# 388_Design_Project_Schematic.net
KiCad netlist of a schematic drawn in EAGLE
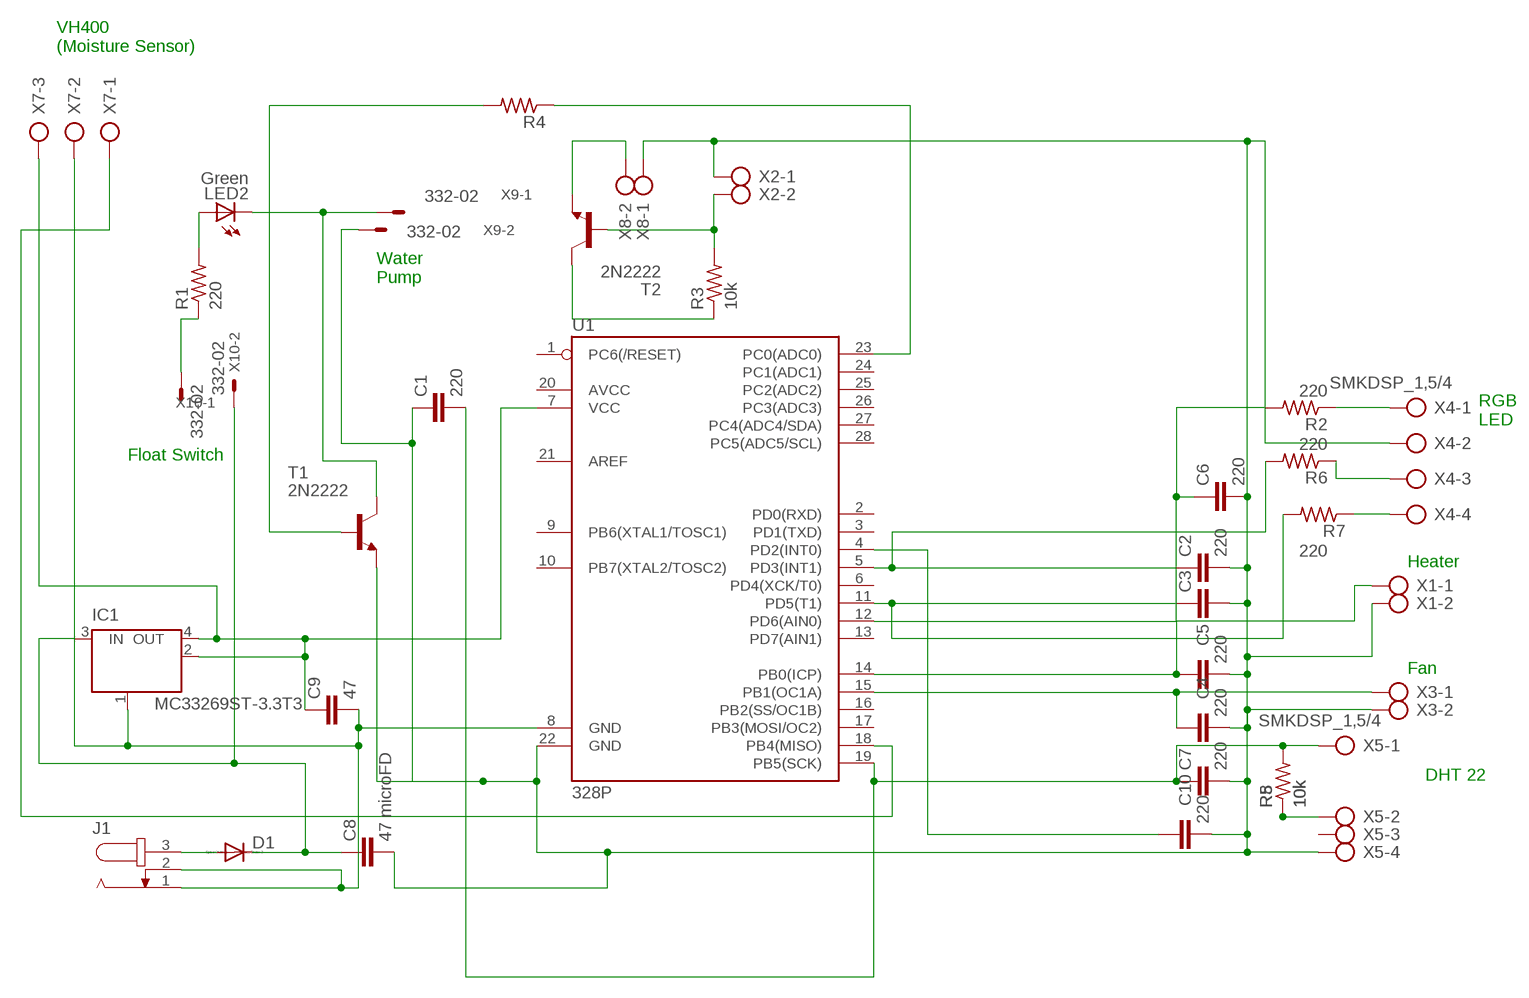
[diagram p0: schematic, sheet 1]

(export (version "E")
  (design (tool "Eeschema 10.0.6"))
  (components
    (comp (ref "C1")
      (value "220")
      (footprint "eagle-import:C025-024X044")
      (libsource (lib "eagle-import") (part "C-EU025-024X044"))
    )
    (comp (ref "C2")
      (value "220")
      (footprint "eagle-import:C025-024X044")
      (libsource (lib "eagle-import") (part "C-EU025-024X044"))
    )
    (comp (ref "C3")
      (value "C-EU025-024X044")
      (footprint "eagle-import:C025-024X044")
      (libsource (lib "eagle-import") (part "C-EU025-024X044"))
    )
    (comp (ref "C4")
      (value "220")
      (footprint "eagle-import:C025-024X044")
      (libsource (lib "eagle-import") (part "C-EU025-024X044"))
    )
    (comp (ref "C5")
      (value "220")
      (footprint "eagle-import:C025-024X044")
      (libsource (lib "eagle-import") (part "C-EU025-024X044"))
    )
    (comp (ref "C6")
      (value "220")
      (footprint "eagle-import:C025-024X044")
      (libsource (lib "eagle-import") (part "C-EU025-024X044"))
    )
    (comp (ref "C7")
      (value "220")
      (footprint "eagle-import:C025-024X044")
      (libsource (lib "eagle-import") (part "C-EU025-024X044"))
    )
    (comp (ref "C8")
      (value "47 microFD")
      (footprint "eagle-import:C025-024X044")
      (libsource (lib "eagle-import") (part "C-EU025-024X044"))
    )
    (comp (ref "C9")
      (value "47")
      (footprint "eagle-import:C025-024X044")
      (libsource (lib "eagle-import") (part "C-EU025-024X044"))
    )
    (comp (ref "C10")
      (value "220")
      (footprint "eagle-import:C025-024X044")
      (libsource (lib "eagle-import") (part "C-EU025-024X044"))
    )
    (comp (ref "D1")
      (value "DIODE-DO214BA")
      (footprint "eagle-import:DO214BA")
      (libsource (lib "eagle-import") (part "DIODE-DO214BA"))
    )
    (comp (ref "IC1")
      (value "MC33269ST-3.3T3")
      (footprint "eagle-import:SOT223")
      (libsource (lib "eagle-import") (part "MC33269ST-3.3T3"))
    )
    (comp (ref "J1")
      (value "JACK-PLUG1")
      (footprint "eagle-import:SPC4078")
      (libsource (lib "eagle-import") (part "JACK-PLUG1"))
    )
    (comp (ref "LED2")
      (value "Green")
      (footprint "eagle-import:CHIPLED_0805")
      (libsource (lib "eagle-import") (part "LEDCHIPLED_0805"))
    )
    (comp (ref "R1")
      (value "220")
      (footprint "eagle-import:R0805")
      (libsource (lib "eagle-import") (part "R-US_R0805"))
    )
    (comp (ref "R2")
      (value "220")
      (footprint "eagle-import:R0805")
      (libsource (lib "eagle-import") (part "R-US_R0805"))
    )
    (comp (ref "R3")
      (value "10k")
      (footprint "eagle-import:R0805")
      (libsource (lib "eagle-import") (part "R-US_R0805"))
    )
    (comp (ref "R4")
      (value "R-US_R0805")
      (footprint "eagle-import:R0805")
      (libsource (lib "eagle-import") (part "R-US_R0805"))
    )
    (comp (ref "R5")
      (value "10k")
      (footprint "eagle-import:R0805")
      (libsource (lib "eagle-import") (part "R-US_R0805"))
    )
    (comp (ref "R6")
      (value "220")
      (footprint "eagle-import:R0805")
      (libsource (lib "eagle-import") (part "R-US_R0805"))
    )
    (comp (ref "R7")
      (value "220")
      (footprint "eagle-import:R0805")
      (libsource (lib "eagle-import") (part "R-US_R0805"))
    )
    (comp (ref "R8")
      (value "10k")
      (footprint "eagle-import:R0805")
      (libsource (lib "eagle-import") (part "R-US_R0805"))
    )
    (comp (ref "T1")
      (value "2N2222")
      (footprint "eagle-import:TO18")
      (libsource (lib "eagle-import") (part "2N2222"))
    )
    (comp (ref "T2")
      (value "2N2222")
      (footprint "eagle-import:TO18")
      (libsource (lib "eagle-import") (part "2N2222"))
    )
    (comp (ref "U1")
      (value "328P")
      (footprint "eagle-import:DIP28")
      (libsource (lib "eagle-import") (part "ATMEGA328P_PDIP"))
    )
    (comp (ref "X1")
      (value "AK300/2")
      (footprint "eagle-import:AK300_2")
      (libsource (lib "eagle-import") (part "AK300/2"))
    )
    (comp (ref "X2")
      (value "AK300/2")
      (footprint "eagle-import:AK300_2")
      (libsource (lib "eagle-import") (part "AK300/2"))
    )
    (comp (ref "X3")
      (value "AK300/2")
      (footprint "eagle-import:AK300_2")
      (libsource (lib "eagle-import") (part "AK300/2"))
    )
    (comp (ref "X4")
      (value "SMKDSP_1,5/4")
      (footprint "eagle-import:SMKDSP_1,5_4")
      (fields (field (name "MF") "FARNELL") (field (name "MPN") "1733596"))
      (libsource (lib "eagle-import") (part "SMKDSP_1,5/4"))
    )
    (comp (ref "X5")
      (value "SMKDSP_1,5/4")
      (footprint "eagle-import:SMKDSP_1,5_4")
      (fields (field (name "MF") "FARNELL") (field (name "MPN") "1733596"))
      (libsource (lib "eagle-import") (part "SMKDSP_1,5/4"))
    )
    (comp (ref "X7")
      (value "AK300/3")
      (footprint "eagle-import:AK300_3")
      (libsource (lib "eagle-import") (part "AK300/3"))
    )
    (comp (ref "X8")
      (value "AK300/2")
      (footprint "eagle-import:AK300_2")
      (libsource (lib "eagle-import") (part "AK300/2"))
    )
    (comp (ref "X9")
      (value "332-02")
      (footprint "eagle-import:332-02")
      (libsource (lib "eagle-import") (part "332-02"))
    )
    (comp (ref "X10")
      (value "332-02")
      (footprint "eagle-import:332-02")
      (libsource (lib "eagle-import") (part "332-02"))
    )
  )
  (nets
    (net (code "1") (name "Net-(D1-PadA)") (class "Default")
      (node (ref "D1") (pin "A") (pinfunction "A_A") (pintype "passive"))
      (node (ref "J1") (pin "3") (pinfunction "3_3") (pintype "passive"))
    )
    (net (code "2") (name "Net-(IC1-GND{slash}ADJ)") (class "Default")
      (node (ref "C9") (pin "2") (pinfunction "2_2") (pintype "passive"))
      (node (ref "IC1") (pin "1") (pinfunction "GND/ADJ_1") (pintype "input"))
      (node (ref "J1") (pin "1") (pinfunction "1_1") (pintype "passive"))
      (node (ref "J1") (pin "2") (pinfunction "2_2") (pintype "passive"))
      (node (ref "U1") (pin "8") (pinfunction "GND_8") (pintype "bidirectional"))
      (node (ref "X7") (pin "2") (pinfunction "KL_2") (pintype "passive"))
    )
    (net (code "3") (name "Net-(IC1-IN)") (class "Default")
      (node (ref "C8") (pin "1") (pinfunction "1_1") (pintype "passive"))
      (node (ref "D1") (pin "C") (pinfunction "C_C") (pintype "passive"))
      (node (ref "IC1") (pin "3") (pinfunction "IN_3") (pintype "input"))
      (node (ref "X10") (pin "2") (pinfunction "S_2") (pintype "passive"))
    )
    (net (code "4") (name "Net-(LED2-PadA)") (class "Default")
      (node (ref "LED2") (pin "A") (pinfunction "A_A") (pintype "passive"))
      (node (ref "R1") (pin "2") (pinfunction "2_2") (pintype "passive"))
    )
    (net (code "5") (name "Net-(T1-B)") (class "Default")
      (node (ref "R4") (pin "2") (pinfunction "2_2") (pintype "passive"))
      (node (ref "T1") (pin "2") (pinfunction "B_2") (pintype "passive"))
    )
    (net (code "6") (name "Net-(T1-C)") (class "Default")
      (node (ref "LED2") (pin "C") (pinfunction "C_C") (pintype "passive"))
      (node (ref "T1") (pin "3") (pinfunction "C_3") (pintype "passive"))
      (node (ref "X9") (pin "1") (pinfunction "S_1") (pintype "passive"))
    )
    (net (code "7") (name "Net-(T1-E)") (class "Default")
      (node (ref "C1") (pin "1") (pinfunction "1_1") (pintype "passive"))
      (node (ref "C10") (pin "2") (pinfunction "2_2") (pintype "passive"))
      (node (ref "C2") (pin "2") (pinfunction "2_2") (pintype "passive"))
      (node (ref "C3") (pin "2") (pinfunction "2_2") (pintype "passive"))
      (node (ref "C4") (pin "2") (pinfunction "2_2") (pintype "passive"))
      (node (ref "C5") (pin "2") (pinfunction "2_2") (pintype "passive"))
      (node (ref "C6") (pin "2") (pinfunction "2_2") (pintype "passive"))
      (node (ref "C7") (pin "2") (pinfunction "2_2") (pintype "passive"))
      (node (ref "C8") (pin "2") (pinfunction "2_2") (pintype "passive"))
      (node (ref "T1") (pin "1") (pinfunction "E_1") (pintype "passive"))
      (node (ref "U1") (pin "22") (pinfunction "GND_22") (pintype "bidirectional"))
      (node (ref "X1") (pin "2") (pinfunction "KL_2") (pintype "passive"))
      (node (ref "X2") (pin "1") (pinfunction "KL_1") (pintype "passive"))
      (node (ref "X3") (pin "2") (pinfunction "KL_2") (pintype "passive"))
      (node (ref "X4") (pin "2") (pinfunction "KL_2") (pintype "passive"))
      (node (ref "X5") (pin "4") (pinfunction "KL_4") (pintype "passive"))
      (node (ref "X8") (pin "1") (pinfunction "KL_1") (pintype "passive"))
      (node (ref "X9") (pin "2") (pinfunction "S_2") (pintype "passive"))
    )
    (net (code "8") (name "Net-(T2-B)") (class "Default")
      (node (ref "R3") (pin "2") (pinfunction "2_2") (pintype "passive"))
      (node (ref "T2") (pin "2") (pinfunction "B_2") (pintype "passive"))
      (node (ref "X2") (pin "2") (pinfunction "KL_2") (pintype "passive"))
    )
    (net (code "9") (name "Net-(T2-C)") (class "Default")
      (node (ref "R3") (pin "1") (pinfunction "1_1") (pintype "passive"))
      (node (ref "T2") (pin "3") (pinfunction "C_3") (pintype "passive"))
    )
    (net (code "10") (name "Net-(T2-E)") (class "Default")
      (node (ref "T2") (pin "1") (pinfunction "E_1") (pintype "passive"))
      (node (ref "X8") (pin "2") (pinfunction "KL_2") (pintype "passive"))
    )
    (net (code "11") (name "Net-(U1-PB0(ICP))") (class "Default")
      (node (ref "C5") (pin "1") (pinfunction "1_1") (pintype "passive"))
      (node (ref "C6") (pin "1") (pinfunction "1_1") (pintype "passive"))
      (node (ref "R2") (pin "2") (pinfunction "2_2") (pintype "passive"))
      (node (ref "U1") (pin "12") (pinfunction "PD6(AIN0)_12") (pintype "bidirectional"))
      (node (ref "U1") (pin "14") (pinfunction "PB0(ICP)_14") (pintype "bidirectional"))
      (node (ref "X1") (pin "1") (pinfunction "KL_1") (pintype "passive"))
    )
    (net (code "12") (name "Net-(U1-PB1(OC1A))") (class "Default")
      (node (ref "C4") (pin "1") (pinfunction "1_1") (pintype "passive"))
      (node (ref "U1") (pin "15") (pinfunction "PB1(OC1A)_15") (pintype "bidirectional"))
      (node (ref "X3") (pin "1") (pinfunction "KL_1") (pintype "passive"))
    )
    (net (code "13") (name "Net-(U1-PB4(MISO))") (class "Default")
      (node (ref "U1") (pin "18") (pinfunction "PB4(MISO)_18") (pintype "bidirectional"))
      (node (ref "X7") (pin "1") (pinfunction "KL_1") (pintype "passive"))
    )
    (net (code "14") (name "Net-(U1-PB5(SCK))") (class "Default")
      (node (ref "C1") (pin "2") (pinfunction "2_2") (pintype "passive"))
      (node (ref "C7") (pin "1") (pinfunction "1_1") (pintype "passive"))
      (node (ref "R5") (pin "2") (pinfunction "2_2") (pintype "passive"))
      (node (ref "R8") (pin "2") (pinfunction "2_2") (pintype "passive"))
      (node (ref "U1") (pin "19") (pinfunction "PB5(SCK)_19") (pintype "bidirectional"))
      (node (ref "X5") (pin "1") (pinfunction "KL_1") (pintype "passive"))
    )
    (net (code "15") (name "Net-(U1-PC0(ADC0))") (class "Default")
      (node (ref "R4") (pin "1") (pinfunction "1_1") (pintype "passive"))
      (node (ref "U1") (pin "23") (pinfunction "PC0(ADC0)_23") (pintype "bidirectional"))
    )
    (net (code "16") (name "Net-(U1-PD2(INT0))") (class "Default")
      (node (ref "C10") (pin "1") (pinfunction "1_1") (pintype "passive"))
      (node (ref "U1") (pin "4") (pinfunction "PD2(INT0)_4") (pintype "bidirectional"))
    )
    (net (code "17") (name "Net-(U1-PD3(INT1))") (class "Default")
      (node (ref "C2") (pin "1") (pinfunction "1_1") (pintype "passive"))
      (node (ref "R6") (pin "2") (pinfunction "2_2") (pintype "passive"))
      (node (ref "U1") (pin "5") (pinfunction "PD3(INT1)_5") (pintype "bidirectional"))
    )
    (net (code "18") (name "Net-(U1-PD5(T1))") (class "Default")
      (node (ref "C3") (pin "1") (pinfunction "1_1") (pintype "passive"))
      (node (ref "R7") (pin "2") (pinfunction "2_2") (pintype "passive"))
      (node (ref "U1") (pin "11") (pinfunction "PD5(T1)_11") (pintype "bidirectional"))
    )
    (net (code "19") (name "Net-(U1-VCC)") (class "Default")
      (node (ref "C9") (pin "1") (pinfunction "1_1") (pintype "passive"))
      (node (ref "IC1") (pin "2") (pinfunction "OUT_2") (pintype "passive"))
      (node (ref "IC1") (pin "4") (pinfunction "OUT_4") (pintype "passive"))
      (node (ref "U1") (pin "7") (pinfunction "VCC_7") (pintype "bidirectional"))
      (node (ref "X7") (pin "3") (pinfunction "KL_3") (pintype "passive"))
    )
    (net (code "20") (name "Net-(X4A-KL)") (class "Default")
      (node (ref "R2") (pin "1") (pinfunction "1_1") (pintype "passive"))
      (node (ref "X4") (pin "1") (pinfunction "KL_1") (pintype "passive"))
    )
    (net (code "21") (name "Net-(X4C-KL)") (class "Default")
      (node (ref "R6") (pin "1") (pinfunction "1_1") (pintype "passive"))
      (node (ref "X4") (pin "3") (pinfunction "KL_3") (pintype "passive"))
    )
    (net (code "22") (name "Net-(X4D-KL)") (class "Default")
      (node (ref "R7") (pin "1") (pinfunction "1_1") (pintype "passive"))
      (node (ref "X4") (pin "4") (pinfunction "KL_4") (pintype "passive"))
    )
    (net (code "23") (name "Net-(X5B-KL)") (class "Default")
      (node (ref "R5") (pin "1") (pinfunction "1_1") (pintype "passive"))
      (node (ref "R8") (pin "1") (pinfunction "1_1") (pintype "passive"))
      (node (ref "X5") (pin "2") (pinfunction "KL_2") (pintype "passive"))
    )
    (net (code "24") (name "Net-(X10A-S)") (class "Default")
      (node (ref "R1") (pin "1") (pinfunction "1_1") (pintype "passive"))
      (node (ref "X10") (pin "1") (pinfunction "S_1") (pintype "passive"))
    )
    (net (code "25") (name "unconnected-(U1-AREF-Pad21)") (class "Default")
      (node (ref "U1") (pin "21") (pinfunction "AREF_21") (pintype "bidirectional"))
    )
    (net (code "26") (name "unconnected-(U1-AVCC-Pad20)") (class "Default")
      (node (ref "U1") (pin "20") (pinfunction "AVCC_20") (pintype "bidirectional"))
    )
    (net (code "27") (name "unconnected-(U1-PB2(SS{slash}OC1B)-Pad16)") (class "Default")
      (node (ref "U1") (pin "16") (pinfunction "PB2(SS/OC1B)_16") (pintype "bidirectional"))
    )
    (net (code "28") (name "unconnected-(U1-PB3(MOSI{slash}OC2)-Pad17)") (class "Default")
      (node (ref "U1") (pin "17") (pinfunction "PB3(MOSI/OC2)_17") (pintype "bidirectional"))
    )
    (net (code "29") (name "unconnected-(U1-PB6(XTAL1{slash}TOSC1)-Pad9)") (class "Default")
      (node (ref "U1") (pin "9") (pinfunction "PB6(XTAL1/TOSC1)_9") (pintype "bidirectional"))
    )
    (net (code "30") (name "unconnected-(U1-PB7(XTAL2{slash}TOSC2)-Pad10)") (class "Default")
      (node (ref "U1") (pin "10") (pinfunction "PB7(XTAL2/TOSC2)_10") (pintype "bidirectional"))
    )
    (net (code "31") (name "unconnected-(U1-PC1(ADC1)-Pad24)") (class "Default")
      (node (ref "U1") (pin "24") (pinfunction "PC1(ADC1)_24") (pintype "bidirectional"))
    )
    (net (code "32") (name "unconnected-(U1-PC2(ADC2)-Pad25)") (class "Default")
      (node (ref "U1") (pin "25") (pinfunction "PC2(ADC2)_25") (pintype "bidirectional"))
    )
    (net (code "33") (name "unconnected-(U1-PC3(ADC3)-Pad26)") (class "Default")
      (node (ref "U1") (pin "26") (pinfunction "PC3(ADC3)_26") (pintype "bidirectional"))
    )
    (net (code "34") (name "unconnected-(U1-PC4(ADC4{slash}SDA)-Pad27)") (class "Default")
      (node (ref "U1") (pin "27") (pinfunction "PC4(ADC4/SDA)_27") (pintype "bidirectional"))
    )
    (net (code "35") (name "unconnected-(U1-PC5(ADC5{slash}SCL)-Pad28)") (class "Default")
      (node (ref "U1") (pin "28") (pinfunction "PC5(ADC5/SCL)_28") (pintype "bidirectional"))
    )
    (net (code "36") (name "unconnected-(U1-PC6({slash}RESET)-Pad1)") (class "Default")
      (node (ref "U1") (pin "1") (pinfunction "PC6(/RESET)_1") (pintype "bidirectional"))
    )
    (net (code "37") (name "unconnected-(U1-PD0(RXD)-Pad2)") (class "Default")
      (node (ref "U1") (pin "2") (pinfunction "PD0(RXD)_2") (pintype "bidirectional"))
    )
    (net (code "38") (name "unconnected-(U1-PD1(TXD)-Pad3)") (class "Default")
      (node (ref "U1") (pin "3") (pinfunction "PD1(TXD)_3") (pintype "bidirectional"))
    )
    (net (code "39") (name "unconnected-(U1-PD4(XCK{slash}T0)-Pad6)") (class "Default")
      (node (ref "U1") (pin "6") (pinfunction "PD4(XCK/T0)_6") (pintype "bidirectional"))
    )
    (net (code "40") (name "unconnected-(U1-PD7(AIN1)-Pad13)") (class "Default")
      (node (ref "U1") (pin "13") (pinfunction "PD7(AIN1)_13") (pintype "bidirectional"))
    )
    (net (code "41") (name "unconnected-(X5C-KL-Pad3)") (class "Default")
      (node (ref "X5") (pin "3") (pinfunction "KL_3") (pintype "passive"))
    )
  )
)
